# STM32F7.net
KiCad netlist of a schematic drawn in Altium Designer
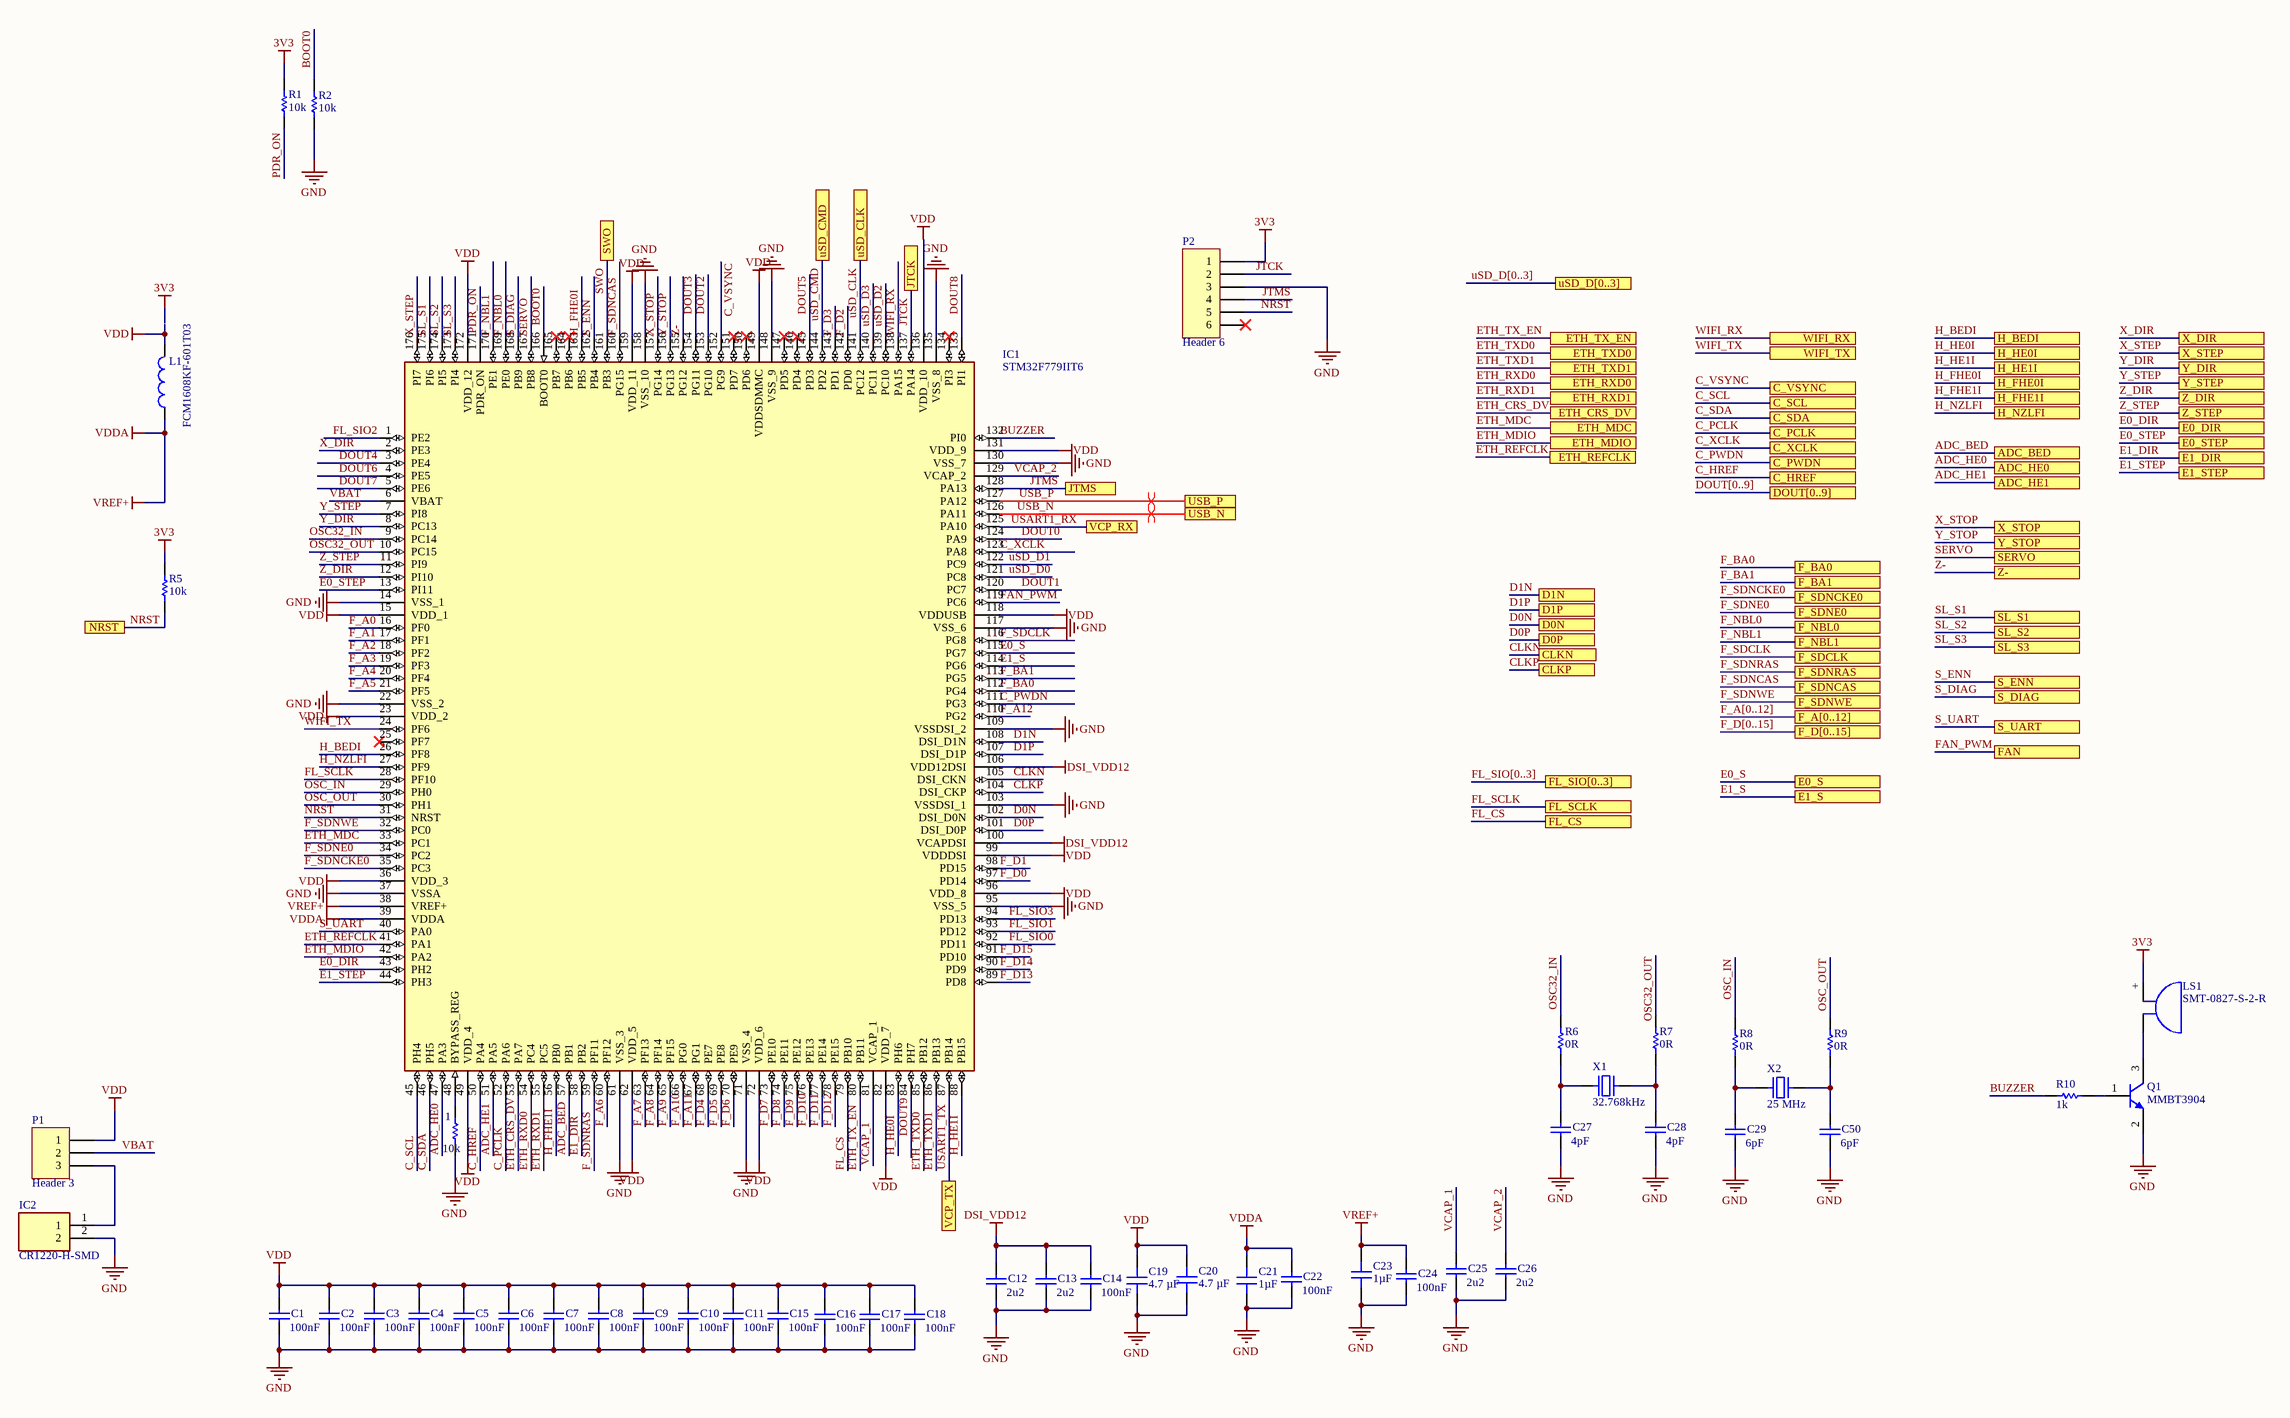
[diagram p0: STM32F7.SchDoc]

(export (version "E")
  (design (tool "Eeschema 10.0.6"))
  (components
    (comp (ref "1")
      (value "10k")
      (footprint "1608[0603]")
      (description "Resistor")
      (fields (field (name "Comment") "Res1") (field (name "PUBLISHER") "Altium Limited"))
      (libsource (lib "Miscellaneous Devices") (part "Res1"))
    )
    (comp (ref "C1")
      (value "100nF")
      (footprint "1608[0603]")
      (description "Capacitor")
      (fields (field (name "Comment") "X5R") (field (name "PUBLISHER") "Altium Limited"))
      (libsource (lib "Miscellaneous Devices") (part "Cap"))
    )
    (comp (ref "C2")
      (value "100nF")
      (footprint "1608[0603]")
      (description "Capacitor")
      (fields (field (name "Comment") "X5R") (field (name "PUBLISHER") "Altium Limited"))
      (libsource (lib "Miscellaneous Devices") (part "Cap"))
    )
    (comp (ref "C3")
      (value "100nF")
      (footprint "1608[0603]")
      (description "Capacitor")
      (fields (field (name "Comment") "X5R") (field (name "PUBLISHER") "Altium Limited"))
      (libsource (lib "Miscellaneous Devices") (part "Cap"))
    )
    (comp (ref "C4")
      (value "100nF")
      (footprint "1608[0603]")
      (description "Capacitor")
      (fields (field (name "Comment") "X5R") (field (name "PUBLISHER") "Altium Limited"))
      (libsource (lib "Miscellaneous Devices") (part "Cap"))
    )
    (comp (ref "C5")
      (value "100nF")
      (footprint "1608[0603]")
      (description "Capacitor")
      (fields (field (name "Comment") "X5R") (field (name "PUBLISHER") "Altium Limited"))
      (libsource (lib "Miscellaneous Devices") (part "Cap"))
    )
    (comp (ref "C6")
      (value "100nF")
      (footprint "1608[0603]")
      (description "Capacitor")
      (fields (field (name "Comment") "X5R") (field (name "PUBLISHER") "Altium Limited"))
      (libsource (lib "Miscellaneous Devices") (part "Cap"))
    )
    (comp (ref "C7")
      (value "100nF")
      (footprint "1608[0603]")
      (description "Capacitor")
      (fields (field (name "Comment") "X5R") (field (name "PUBLISHER") "Altium Limited"))
      (libsource (lib "Miscellaneous Devices") (part "Cap"))
    )
    (comp (ref "C8")
      (value "100nF")
      (footprint "1608[0603]")
      (description "Capacitor")
      (fields (field (name "Comment") "X5R") (field (name "PUBLISHER") "Altium Limited"))
      (libsource (lib "Miscellaneous Devices") (part "Cap"))
    )
    (comp (ref "C9")
      (value "100nF")
      (footprint "1608[0603]")
      (description "Capacitor")
      (fields (field (name "Comment") "X5R") (field (name "PUBLISHER") "Altium Limited"))
      (libsource (lib "Miscellaneous Devices") (part "Cap"))
    )
    (comp (ref "C10")
      (value "100nF")
      (footprint "1608[0603]")
      (description "Capacitor")
      (fields (field (name "Comment") "X5R") (field (name "PUBLISHER") "Altium Limited"))
      (libsource (lib "Miscellaneous Devices") (part "Cap"))
    )
    (comp (ref "C11")
      (value "100nF")
      (footprint "1608[0603]")
      (description "Capacitor")
      (fields (field (name "Comment") "X5R") (field (name "PUBLISHER") "Altium Limited"))
      (libsource (lib "Miscellaneous Devices") (part "Cap"))
    )
    (comp (ref "C12")
      (value "2u2")
      (footprint "1608[0603]")
      (description "Capacitor")
      (fields (field (name "Comment") "X5R") (field (name "PUBLISHER") "Altium Limited"))
      (libsource (lib "Miscellaneous Devices") (part "Cap"))
    )
    (comp (ref "C13")
      (value "2u2")
      (footprint "1608[0603]")
      (description "Capacitor")
      (fields (field (name "Comment") "X5R") (field (name "PUBLISHER") "Altium Limited"))
      (libsource (lib "Miscellaneous Devices") (part "Cap"))
    )
    (comp (ref "C14")
      (value "100nF")
      (footprint "1608[0603]")
      (description "Capacitor")
      (fields (field (name "Comment") "X5R") (field (name "PUBLISHER") "Altium Limited"))
      (libsource (lib "Miscellaneous Devices") (part "Cap"))
    )
    (comp (ref "C15")
      (value "100nF")
      (footprint "1608[0603]")
      (description "Capacitor")
      (fields (field (name "Comment") "X5R") (field (name "PUBLISHER") "Altium Limited"))
      (libsource (lib "Miscellaneous Devices") (part "Cap"))
    )
    (comp (ref "C16")
      (value "100nF")
      (footprint "1608[0603]")
      (description "Capacitor")
      (fields (field (name "Comment") "X5R") (field (name "PUBLISHER") "Altium Limited"))
      (libsource (lib "Miscellaneous Devices") (part "Cap"))
    )
    (comp (ref "C17")
      (value "100nF")
      (footprint "1608[0603]")
      (description "Capacitor")
      (fields (field (name "Comment") "X5R") (field (name "PUBLISHER") "Altium Limited"))
      (libsource (lib "Miscellaneous Devices") (part "Cap"))
    )
    (comp (ref "C18")
      (value "100nF")
      (footprint "1608[0603]")
      (description "Capacitor")
      (fields (field (name "Comment") "X5R") (field (name "PUBLISHER") "Altium Limited"))
      (libsource (lib "Miscellaneous Devices") (part "Cap"))
    )
    (comp (ref "C19")
      (value "4.7 µF")
      (footprint "CAP 0603_1608")
      (description "CAP CER 4.7UF 16V X5R 0603")
      (fields
        (field (name "PART NUMBER") "GRM185R61C475KE11D")
        (field (name "MANUFACTURER") "Murata Electronics")
      )
      (libsource (lib "Celestial Altium Library - altium_library") (part "Capacitor"))
    )
    (comp (ref "C20")
      (value "4.7 µF")
      (footprint "CAP 0603_1608")
      (description "CAP CER 4.7UF 16V X5R 0603")
      (fields
        (field (name "PART NUMBER") "GRM185R61C475KE11D")
        (field (name "MANUFACTURER") "Murata Electronics")
      )
      (libsource (lib "Celestial Altium Library - altium_library") (part "Capacitor"))
    )
    (comp (ref "C21")
      (value "1µF")
      (footprint "CAP 0603_1608")
      (description "CAP CER 1UF 16V X5R 0603")
      (fields (field (name "PART NUMBER") "0603YD105KAT4A") (field (name "MANUFACTURER") "AVX Corporation"))
      (libsource (lib "Celestial Altium Library - altium_library") (part "Capacitor"))
    )
    (comp (ref "C22")
      (value "100nF")
      (footprint "1608[0603]")
      (description "Capacitor")
      (fields (field (name "Comment") "X5R") (field (name "PUBLISHER") "Altium Limited"))
      (libsource (lib "Miscellaneous Devices") (part "Cap"))
    )
    (comp (ref "C23")
      (value "1µF")
      (footprint "CAP 0603_1608")
      (description "CAP CER 1UF 16V X5R 0603")
      (fields (field (name "PART NUMBER") "0603YD105KAT4A") (field (name "MANUFACTURER") "AVX Corporation"))
      (libsource (lib "Celestial Altium Library - altium_library") (part "Capacitor"))
    )
    (comp (ref "C24")
      (value "100nF")
      (footprint "1608[0603]")
      (description "Capacitor")
      (fields (field (name "Comment") "X5R") (field (name "PUBLISHER") "Altium Limited"))
      (libsource (lib "Miscellaneous Devices") (part "Cap"))
    )
    (comp (ref "C25")
      (value "2u2")
      (footprint "1608[0603]")
      (description "Capacitor")
      (fields (field (name "Comment") "X5R") (field (name "PUBLISHER") "Altium Limited"))
      (libsource (lib "Miscellaneous Devices") (part "Cap"))
    )
    (comp (ref "C26")
      (value "2u2")
      (footprint "1608[0603]")
      (description "Capacitor")
      (fields (field (name "Comment") "X5R") (field (name "PUBLISHER") "Altium Limited"))
      (libsource (lib "Miscellaneous Devices") (part "Cap"))
    )
    (comp (ref "C27")
      (value "4pF")
      (footprint "1608[0603]")
      (description "Capacitor")
      (fields (field (name "Comment") "X5R") (field (name "PUBLISHER") "Altium Limited"))
      (libsource (lib "Miscellaneous Devices") (part "Cap"))
    )
    (comp (ref "C28")
      (value "4pF")
      (footprint "1608[0603]")
      (description "Capacitor")
      (fields (field (name "Comment") "X5R") (field (name "PUBLISHER") "Altium Limited"))
      (libsource (lib "Miscellaneous Devices") (part "Cap"))
    )
    (comp (ref "C29")
      (value "6pF")
      (footprint "1608[0603]")
      (description "Capacitor")
      (fields (field (name "Comment") "X5R") (field (name "PUBLISHER") "Altium Limited"))
      (libsource (lib "Miscellaneous Devices") (part "Cap"))
    )
    (comp (ref "C50")
      (value "6pF")
      (footprint "1608[0603]")
      (description "Capacitor")
      (fields (field (name "Comment") "X5R") (field (name "PUBLISHER") "Altium Limited"))
      (libsource (lib "Miscellaneous Devices") (part "Cap"))
    )
    (comp (ref "IC1")
      (value "STM32F779IIT6")
      (footprint "SamacSys:QFP50P2600X2600X160-176N")
      (description "Integrated Circuit")
      (fields (field (name "MOUSER PART NUMBER") "511-STM32F779IIT6"))
      (libsource (lib "*") (part "STM32F779IIT6"))
    )
    (comp (ref "IC2")
      (value "CR1220-H-SMD")
      (footprint "SamacSys:CR1220HSMD")
      (description "Integrated Circuit")
      (libsource (lib "*") (part "CR1220-H-SMD"))
    )
    (comp (ref "L1")
      (value "FCM1608KF-601T03")
      (footprint "0603L")
      (description "Inductor")
      (fields (field (name "PUBLISHER") "Altium Limited"))
      (libsource (lib "MB1137") (part "Inductor"))
    )
    (comp (ref "LS1")
      (value "SMT-0827-S-2-R")
      (footprint "PUI Audio SMT-0827-S-2-R")
      (description "AUDIO MAGNETIC XDCR 2.5-4.5V SMD")
      (fields (field (name "MANUFACTURER") "PUI Audio, Inc."))
      (libsource (lib "Celestial Altium Library - altium_library") (part "Buzzer 2 pin"))
    )
    (comp (ref "P1")
      (value "Header 3")
      (footprint "HDR1X3")
      (description "Header, 3-Pin")
      (fields (field (name "PUBLISHER") "Altium Limited"))
      (libsource (lib "Miscellaneous Connectors") (part "Header 3"))
    )
    (comp (ref "P2")
      (value "Header 6")
      (footprint "HDR1X6")
      (description "Header, 6-Pin")
      (fields (field (name "PUBLISHER") "Altium Limited"))
      (libsource (lib "Miscellaneous Connectors") (part "Header 6"))
    )
    (comp (ref "Q1")
      (value "MMBT3904")
      (footprint "SOT-23_N")
      (description "TRANS NPN 40V 0.2A SOT416")
      (fields (field (name "PART NUMBER") "MMBT3904TT1G") (field (name "MANUFACTURER") "ON Semiconductor"))
      (libsource (lib "Celestial Altium Library - altium_library") (part "ON SEMI NPN SC-75"))
    )
    (comp (ref "R1")
      (value "10k")
      (footprint "1608[0603]")
      (description "Resistor")
      (fields (field (name "Comment") "Res1") (field (name "PUBLISHER") "Altium Limited"))
      (libsource (lib "Miscellaneous Devices") (part "Res1"))
    )
    (comp (ref "R2")
      (value "10k")
      (footprint "1608[0603]")
      (description "Resistor")
      (fields (field (name "Comment") "Res1") (field (name "PUBLISHER") "Altium Limited"))
      (libsource (lib "Miscellaneous Devices") (part "Res1"))
    )
    (comp (ref "R5")
      (value "10k")
      (footprint "1608[0603]")
      (description "Resistor")
      (fields (field (name "Comment") "Res1") (field (name "PUBLISHER") "Altium Limited"))
      (libsource (lib "Miscellaneous Devices") (part "Res1"))
    )
    (comp (ref "R6")
      (value "0R")
      (footprint "1608[0603]")
      (description "Resistor")
      (fields (field (name "Comment") "Res1") (field (name "PUBLISHER") "Altium Limited"))
      (libsource (lib "Miscellaneous Devices") (part "Res1"))
    )
    (comp (ref "R7")
      (value "0R")
      (footprint "1608[0603]")
      (description "Resistor")
      (fields (field (name "Comment") "Res1") (field (name "PUBLISHER") "Altium Limited"))
      (libsource (lib "Miscellaneous Devices") (part "Res1"))
    )
    (comp (ref "R8")
      (value "0R")
      (footprint "1608[0603]")
      (description "Resistor")
      (fields (field (name "Comment") "Res1") (field (name "PUBLISHER") "Altium Limited"))
      (libsource (lib "Miscellaneous Devices") (part "Res1"))
    )
    (comp (ref "R9")
      (value "0R")
      (footprint "1608[0603]")
      (description "Resistor")
      (fields (field (name "Comment") "Res1") (field (name "PUBLISHER") "Altium Limited"))
      (libsource (lib "Miscellaneous Devices") (part "Res1"))
    )
    (comp (ref "R10")
      (value "1k")
      (footprint "1608[0603]")
      (description "Resistor")
      (fields (field (name "Comment") "Res1") (field (name "PUBLISHER") "Altium Limited"))
      (libsource (lib "Miscellaneous Devices") (part "Res1"))
    )
    (comp (ref "X1")
      (value "32.768kHz")
      (footprint "NDK NX5032GA")
      (description "CRYSTAL 25.0000MHZ 8PF SMD")
      (fields
        (field (name "PART NUMBER") "NX5032GA-25.000000MHZ-LN-CD-1")
        (field (name "MANUFACTURER") "NDK America, Inc.")
      )
      (libsource (lib "Celestial Altium Library - altium_library") (part "NDK Crystal NX5032GA"))
    )
    (comp (ref "X2")
      (value "25 MHz")
      (footprint "NDK NX5032GA")
      (description "CRYSTAL 25.0000MHZ 8PF SMD")
      (fields
        (field (name "PART NUMBER") "NX5032GA-25.000000MHZ-LN-CD-1")
        (field (name "MANUFACTURER") "NDK America, Inc.")
      )
      (libsource (lib "Celestial Altium Library - altium_library") (part "NDK Crystal NX5032GA"))
    )
  )
  (nets
    (net (code "1") (name "/ADC_BED") (class "Default")
      (node (ref "IC1") (pin "57") (pinfunction "PB1_57") (pintype "bidirectional"))
    )
    (net (code "2") (name "/ADC_HE0") (class "Default")
      (node (ref "IC1") (pin "47") (pinfunction "PA3_47") (pintype "bidirectional"))
    )
    (net (code "3") (name "/ADC_HE1") (class "Default")
      (node (ref "IC1") (pin "51") (pinfunction "PA5_51") (pintype "bidirectional"))
    )
    (net (code "4") (name "/BOOT0") (class "Default")
      (node (ref "IC1") (pin "166") (pinfunction "BOOT0_166") (pintype "input"))
      (node (ref "R2") (pin "1") (pinfunction "1_1") (pintype "passive"))
    )
    (net (code "5") (name "/BUZZER") (class "Default")
      (node (ref "IC1") (pin "132") (pinfunction "PI0_132") (pintype "bidirectional"))
      (node (ref "R10") (pin "1") (pinfunction "1_1") (pintype "passive"))
    )
    (net (code "6") (name "/CLKN") (class "Default")
      (node (ref "IC1") (pin "105") (pinfunction "DSI_CKN_105") (pintype "bidirectional"))
    )
    (net (code "7") (name "/CLKP") (class "Default")
      (node (ref "IC1") (pin "104") (pinfunction "DSI_CKP_104") (pintype "bidirectional"))
    )
    (net (code "8") (name "/C_HREF") (class "Default")
      (node (ref "IC1") (pin "50") (pinfunction "PA4_50") (pintype "bidirectional"))
    )
    (net (code "9") (name "/C_PCLK") (class "Default")
      (node (ref "IC1") (pin "52") (pinfunction "PA6_52") (pintype "bidirectional"))
    )
    (net (code "10") (name "/C_PWDN") (class "Default")
      (node (ref "IC1") (pin "111") (pinfunction "PG3_111") (pintype "bidirectional"))
    )
    (net (code "11") (name "/C_SCL") (class "Default")
      (node (ref "IC1") (pin "45") (pinfunction "PH4_45") (pintype "bidirectional"))
    )
    (net (code "12") (name "/C_SDA") (class "Default")
      (node (ref "IC1") (pin "46") (pinfunction "PH5_46") (pintype "bidirectional"))
    )
    (net (code "13") (name "/C_VSYNC") (class "Default")
      (node (ref "IC1") (pin "152") (pinfunction "PG9_152") (pintype "bidirectional"))
    )
    (net (code "14") (name "/C_XCLK") (class "Default")
      (node (ref "IC1") (pin "123") (pinfunction "PA8_123") (pintype "bidirectional"))
    )
    (net (code "15") (name "/D0N") (class "Default")
      (node (ref "IC1") (pin "102") (pinfunction "DSI_D0N_102") (pintype "bidirectional"))
    )
    (net (code "16") (name "/D0P") (class "Default")
      (node (ref "IC1") (pin "101") (pinfunction "DSI_D0P_101") (pintype "bidirectional"))
    )
    (net (code "17") (name "/D1N") (class "Default")
      (node (ref "IC1") (pin "108") (pinfunction "DSI_D1N_108") (pintype "bidirectional"))
    )
    (net (code "18") (name "/D1P") (class "Default")
      (node (ref "IC1") (pin "107") (pinfunction "DSI_D1P_107") (pintype "bidirectional"))
    )
    (net (code "19") (name "/DOUT0") (class "Default")
      (node (ref "IC1") (pin "124") (pinfunction "PA9_124") (pintype "bidirectional"))
    )
    (net (code "20") (name "/DOUT1") (class "Default")
      (node (ref "IC1") (pin "120") (pinfunction "PC7_120") (pintype "bidirectional"))
    )
    (net (code "21") (name "/DOUT2") (class "Default")
      (node (ref "IC1") (pin "153") (pinfunction "PG10_153") (pintype "bidirectional"))
    )
    (net (code "22") (name "/DOUT3") (class "Default")
      (node (ref "IC1") (pin "154") (pinfunction "PG11_154") (pintype "bidirectional"))
    )
    (net (code "23") (name "/DOUT4") (class "Default")
      (node (ref "IC1") (pin "3") (pinfunction "PE4_3") (pintype "bidirectional"))
    )
    (net (code "24") (name "/DOUT5") (class "Default")
      (node (ref "IC1") (pin "145") (pinfunction "PD3_145") (pintype "bidirectional"))
    )
    (net (code "25") (name "/DOUT6") (class "Default")
      (node (ref "IC1") (pin "4") (pinfunction "PE5_4") (pintype "bidirectional"))
    )
    (net (code "26") (name "/DOUT7") (class "Default")
      (node (ref "IC1") (pin "5") (pinfunction "PE6_5") (pintype "bidirectional"))
    )
    (net (code "27") (name "/DOUT8") (class "Default")
      (node (ref "IC1") (pin "133") (pinfunction "PI1_133") (pintype "bidirectional"))
    )
    (net (code "28") (name "/DOUT9") (class "Default")
      (node (ref "IC1") (pin "84") (pinfunction "PH7_84") (pintype "bidirectional"))
    )
    (net (code "30") (name "/E0_DIR") (class "Default")
      (node (ref "IC1") (pin "43") (pinfunction "PH2_43") (pintype "bidirectional"))
    )
    (net (code "31") (name "/E0_S") (class "Default")
      (node (ref "IC1") (pin "115") (pinfunction "PG7_115") (pintype "bidirectional"))
    )
    (net (code "32") (name "/E0_STEP") (class "Default")
      (node (ref "IC1") (pin "13") (pinfunction "PI11_13") (pintype "bidirectional"))
    )
    (net (code "33") (name "/E1_DIR") (class "Default")
      (node (ref "IC1") (pin "58") (pinfunction "PB2_58") (pintype "bidirectional"))
    )
    (net (code "34") (name "/E1_S") (class "Default")
      (node (ref "IC1") (pin "114") (pinfunction "PG6_114") (pintype "bidirectional"))
    )
    (net (code "35") (name "/E1_STEP") (class "Default")
      (node (ref "IC1") (pin "44") (pinfunction "PH3_44") (pintype "bidirectional"))
    )
    (net (code "36") (name "/ETH_CRS_DV") (class "Default")
      (node (ref "IC1") (pin "53") (pinfunction "PA7_53") (pintype "bidirectional"))
    )
    (net (code "37") (name "/ETH_MDC") (class "Default")
      (node (ref "IC1") (pin "33") (pinfunction "PC1_33") (pintype "bidirectional"))
    )
    (net (code "38") (name "/ETH_MDIO") (class "Default")
      (node (ref "IC1") (pin "42") (pinfunction "PA2_42") (pintype "bidirectional"))
    )
    (net (code "39") (name "/ETH_REFCLK") (class "Default")
      (node (ref "IC1") (pin "41") (pinfunction "PA1_41") (pintype "bidirectional"))
    )
    (net (code "40") (name "/ETH_RXD0") (class "Default")
      (node (ref "IC1") (pin "54") (pinfunction "PC4_54") (pintype "bidirectional"))
    )
    (net (code "41") (name "/ETH_RXD1") (class "Default")
      (node (ref "IC1") (pin "55") (pinfunction "PC5_55") (pintype "bidirectional"))
    )
    (net (code "42") (name "/ETH_TXD0") (class "Default")
      (node (ref "IC1") (pin "85") (pinfunction "PB12_85") (pintype "bidirectional"))
    )
    (net (code "43") (name "/ETH_TXD1") (class "Default")
      (node (ref "IC1") (pin "86") (pinfunction "PB13_86") (pintype "bidirectional"))
    )
    (net (code "44") (name "/ETH_TX_EN") (class "Default")
      (node (ref "IC1") (pin "80") (pinfunction "PB11_80") (pintype "bidirectional"))
    )
    (net (code "45") (name "/FAN_PWM") (class "Default")
      (node (ref "IC1") (pin "119") (pinfunction "PC6_119") (pintype "bidirectional"))
    )
    (net (code "46") (name "/FL_CS") (class "Default")
      (node (ref "IC1") (pin "79") (pinfunction "PB10_79") (pintype "bidirectional"))
    )
    (net (code "47") (name "/FL_SCLK") (class "Default")
      (node (ref "IC1") (pin "28") (pinfunction "PF10_28") (pintype "bidirectional"))
    )
    (net (code "48") (name "/FL_SIO0") (class "Default")
      (node (ref "IC1") (pin "92") (pinfunction "PD11_92") (pintype "bidirectional"))
    )
    (net (code "49") (name "/FL_SIO1") (class "Default")
      (node (ref "IC1") (pin "93") (pinfunction "PD12_93") (pintype "bidirectional"))
    )
    (net (code "50") (name "/FL_SIO2") (class "Default")
      (node (ref "IC1") (pin "1") (pinfunction "PE2_1") (pintype "bidirectional"))
    )
    (net (code "51") (name "/FL_SIO3") (class "Default")
      (node (ref "IC1") (pin "94") (pinfunction "PD13_94") (pintype "bidirectional"))
    )
    (net (code "53") (name "/F_A0") (class "Default")
      (node (ref "IC1") (pin "16") (pinfunction "PF0_16") (pintype "bidirectional"))
    )
    (net (code "54") (name "/F_A1") (class "Default")
      (node (ref "IC1") (pin "17") (pinfunction "PF1_17") (pintype "bidirectional"))
    )
    (net (code "55") (name "/F_A2") (class "Default")
      (node (ref "IC1") (pin "18") (pinfunction "PF2_18") (pintype "bidirectional"))
    )
    (net (code "56") (name "/F_A3") (class "Default")
      (node (ref "IC1") (pin "19") (pinfunction "PF3_19") (pintype "bidirectional"))
    )
    (net (code "57") (name "/F_A4") (class "Default")
      (node (ref "IC1") (pin "20") (pinfunction "PF4_20") (pintype "bidirectional"))
    )
    (net (code "58") (name "/F_A5") (class "Default")
      (node (ref "IC1") (pin "21") (pinfunction "PF5_21") (pintype "bidirectional"))
    )
    (net (code "59") (name "/F_A6") (class "Default")
      (node (ref "IC1") (pin "60") (pinfunction "PF12_60") (pintype "bidirectional"))
    )
    (net (code "60") (name "/F_A7") (class "Default")
      (node (ref "IC1") (pin "63") (pinfunction "PF13_63") (pintype "bidirectional"))
    )
    (net (code "61") (name "/F_A8") (class "Default")
      (node (ref "IC1") (pin "64") (pinfunction "PF14_64") (pintype "bidirectional"))
    )
    (net (code "62") (name "/F_A9") (class "Default")
      (node (ref "IC1") (pin "65") (pinfunction "PF15_65") (pintype "bidirectional"))
    )
    (net (code "63") (name "/F_A10") (class "Default")
      (node (ref "IC1") (pin "66") (pinfunction "PG0_66") (pintype "bidirectional"))
    )
    (net (code "64") (name "/F_A11") (class "Default")
      (node (ref "IC1") (pin "67") (pinfunction "PG1_67") (pintype "bidirectional"))
    )
    (net (code "65") (name "/F_A12") (class "Default")
      (node (ref "IC1") (pin "110") (pinfunction "PG2_110") (pintype "bidirectional"))
    )
    (net (code "67") (name "/F_BA0") (class "Default")
      (node (ref "IC1") (pin "112") (pinfunction "PG4_112") (pintype "bidirectional"))
    )
    (net (code "68") (name "/F_BA1") (class "Default")
      (node (ref "IC1") (pin "113") (pinfunction "PG5_113") (pintype "bidirectional"))
    )
    (net (code "69") (name "/F_D0") (class "Default")
      (node (ref "IC1") (pin "97") (pinfunction "PD14_97") (pintype "bidirectional"))
    )
    (net (code "70") (name "/F_D1") (class "Default")
      (node (ref "IC1") (pin "98") (pinfunction "PD15_98") (pintype "bidirectional"))
    )
    (net (code "71") (name "/F_D2") (class "Default")
      (node (ref "IC1") (pin "142") (pinfunction "PD0_142") (pintype "bidirectional"))
    )
    (net (code "72") (name "/F_D3") (class "Default")
      (node (ref "IC1") (pin "143") (pinfunction "PD1_143") (pintype "bidirectional"))
    )
    (net (code "73") (name "/F_D4") (class "Default")
      (node (ref "IC1") (pin "68") (pinfunction "PE7_68") (pintype "bidirectional"))
    )
    (net (code "74") (name "/F_D5") (class "Default")
      (node (ref "IC1") (pin "69") (pinfunction "PE8_69") (pintype "bidirectional"))
    )
    (net (code "75") (name "/F_D6") (class "Default")
      (node (ref "IC1") (pin "70") (pinfunction "PE9_70") (pintype "bidirectional"))
    )
    (net (code "76") (name "/F_D7") (class "Default")
      (node (ref "IC1") (pin "73") (pinfunction "PE10_73") (pintype "bidirectional"))
    )
    (net (code "77") (name "/F_D8") (class "Default")
      (node (ref "IC1") (pin "74") (pinfunction "PE11_74") (pintype "bidirectional"))
    )
    (net (code "78") (name "/F_D9") (class "Default")
      (node (ref "IC1") (pin "75") (pinfunction "PE12_75") (pintype "bidirectional"))
    )
    (net (code "79") (name "/F_D10") (class "Default")
      (node (ref "IC1") (pin "76") (pinfunction "PE13_76") (pintype "bidirectional"))
    )
    (net (code "80") (name "/F_D11") (class "Default")
      (node (ref "IC1") (pin "77") (pinfunction "PE14_77") (pintype "bidirectional"))
    )
    (net (code "81") (name "/F_D12") (class "Default")
      (node (ref "IC1") (pin "78") (pinfunction "PE15_78") (pintype "bidirectional"))
    )
    (net (code "82") (name "/F_D13") (class "Default")
      (node (ref "IC1") (pin "89") (pinfunction "PD8_89") (pintype "bidirectional"))
    )
    (net (code "83") (name "/F_D14") (class "Default")
      (node (ref "IC1") (pin "90") (pinfunction "PD9_90") (pintype "bidirectional"))
    )
    (net (code "84") (name "/F_D15") (class "Default")
      (node (ref "IC1") (pin "91") (pinfunction "PD10_91") (pintype "bidirectional"))
    )
    (net (code "86") (name "/F_NBL0") (class "Default")
      (node (ref "IC1") (pin "169") (pinfunction "PE0_169") (pintype "bidirectional"))
    )
    (net (code "87") (name "/F_NBL1") (class "Default")
      (node (ref "IC1") (pin "170") (pinfunction "PE1_170") (pintype "bidirectional"))
    )
    (net (code "88") (name "/F_SDCLK") (class "Default")
      (node (ref "IC1") (pin "116") (pinfunction "PG8_116") (pintype "bidirectional"))
    )
    (net (code "89") (name "/F_SDNCAS") (class "Default")
      (node (ref "IC1") (pin "160") (pinfunction "PG15_160") (pintype "bidirectional"))
    )
    (net (code "90") (name "/F_SDNCKE0") (class "Default")
      (node (ref "IC1") (pin "35") (pinfunction "PC3_35") (pintype "bidirectional"))
    )
    (net (code "91") (name "/F_SDNE0") (class "Default")
      (node (ref "IC1") (pin "34") (pinfunction "PC2_34") (pintype "bidirectional"))
    )
    (net (code "92") (name "/F_SDNRAS") (class "Default")
      (node (ref "IC1") (pin "59") (pinfunction "PF11_59") (pintype "bidirectional"))
    )
    (net (code "93") (name "/F_SDNWE") (class "Default")
      (node (ref "IC1") (pin "32") (pinfunction "PC0_32") (pintype "bidirectional"))
    )
    (net (code "94") (name "/H_BEDI") (class "Default")
      (node (ref "IC1") (pin "26") (pinfunction "PF8_26") (pintype "bidirectional"))
    )
    (net (code "95") (name "/H_FHE0I") (class "Default")
      (node (ref "IC1") (pin "163") (pinfunction "PB5_163") (pintype "bidirectional"))
    )
    (net (code "96") (name "/H_FHE1I") (class "Default")
      (node (ref "IC1") (pin "56") (pinfunction "PB0_56") (pintype "bidirectional"))
    )
    (net (code "97") (name "/H_HE0I") (class "Default")
      (node (ref "IC1") (pin "83") (pinfunction "PH6_83") (pintype "bidirectional"))
    )
    (net (code "98") (name "/H_HE1I") (class "Default")
      (node (ref "IC1") (pin "88") (pinfunction "PB15_88") (pintype "bidirectional"))
    )
    (net (code "99") (name "/H_NZLFI") (class "Default")
      (node (ref "IC1") (pin "27") (pinfunction "PF9_27") (pintype "bidirectional"))
    )
    (net (code "100") (name "/JTCK") (class "Default")
      (node (ref "IC1") (pin "137") (pinfunction "PA14_137") (pintype "bidirectional"))
      (node (ref "P2") (pin "2") (pinfunction "2_2") (pintype "passive"))
    )
    (net (code "101") (name "/JTMS") (class "Default")
      (node (ref "IC1") (pin "128") (pinfunction "PA13_128") (pintype "bidirectional"))
      (node (ref "P2") (pin "4") (pinfunction "4_4") (pintype "passive"))
    )
    (net (code "102") (name "/NRST") (class "Default")
      (node (ref "IC1") (pin "31") (pinfunction "NRST_31") (pintype "bidirectional"))
      (node (ref "P2") (pin "5") (pinfunction "5_5") (pintype "passive"))
      (node (ref "R5") (pin "2") (pinfunction "2_2") (pintype "passive"))
    )
    (net (code "103") (name "/OSC32_IN") (class "Default")
      (node (ref "IC1") (pin "9") (pinfunction "PC14_9") (pintype "bidirectional"))
      (node (ref "R6") (pin "1") (pinfunction "1_1") (pintype "passive"))
    )
    (net (code "104") (name "/OSC32_OUT") (class "Default")
      (node (ref "IC1") (pin "10") (pinfunction "PC15_10") (pintype "bidirectional"))
      (node (ref "R7") (pin "1") (pinfunction "1_1") (pintype "passive"))
    )
    (net (code "105") (name "/OSC_IN") (class "Default")
      (node (ref "IC1") (pin "29") (pinfunction "PH0_29") (pintype "bidirectional"))
      (node (ref "R8") (pin "1") (pinfunction "1_1") (pintype "passive"))
    )
    (net (code "106") (name "/OSC_OUT") (class "Default")
      (node (ref "IC1") (pin "30") (pinfunction "PH1_30") (pintype "bidirectional"))
      (node (ref "R9") (pin "1") (pinfunction "1_1") (pintype "passive"))
    )
    (net (code "107") (name "/PDR_ON") (class "Default")
      (node (ref "IC1") (pin "171") (pinfunction "PDR_ON_171") (pintype "power_in"))
      (node (ref "R1") (pin "2") (pinfunction "2_2") (pintype "passive"))
    )
    (net (code "108") (name "/SERVO") (class "Default")
      (node (ref "IC1") (pin "167") (pinfunction "PB8_167") (pintype "bidirectional"))
    )
    (net (code "109") (name "/SL_S1") (class "Default")
      (node (ref "IC1") (pin "175") (pinfunction "PI6_175") (pintype "bidirectional"))
    )
    (net (code "110") (name "/SL_S2") (class "Default")
      (node (ref "IC1") (pin "174") (pinfunction "PI5_174") (pintype "bidirectional"))
    )
    (net (code "111") (name "/SL_S3") (class "Default")
      (node (ref "IC1") (pin "173") (pinfunction "PI4_173") (pintype "bidirectional"))
    )
    (net (code "112") (name "/SWO") (class "Default")
      (node (ref "IC1") (pin "161") (pinfunction "PB3_161") (pintype "bidirectional"))
    )
    (net (code "113") (name "/S_DIAG") (class "Default")
      (node (ref "IC1") (pin "168") (pinfunction "PB9_168") (pintype "bidirectional"))
    )
    (net (code "114") (name "/S_ENN") (class "Default")
      (node (ref "IC1") (pin "162") (pinfunction "PB4_162") (pintype "bidirectional"))
    )
    (net (code "115") (name "/S_UART") (class "Default")
      (node (ref "IC1") (pin "40") (pinfunction "PA0_40") (pintype "bidirectional"))
    )
    (net (code "116") (name "/USART1_RX") (class "Default")
      (node (ref "IC1") (pin "125") (pinfunction "PA10_125") (pintype "bidirectional"))
    )
    (net (code "117") (name "/USART1_TX") (class "Default")
      (node (ref "IC1") (pin "87") (pinfunction "PB14_87") (pintype "bidirectional"))
    )
    (net (code "118") (name "/USB_N") (class "Default")
      (node (ref "IC1") (pin "126") (pinfunction "PA11_126") (pintype "bidirectional"))
    )
    (net (code "119") (name "/USB_P") (class "Default")
      (node (ref "IC1") (pin "127") (pinfunction "PA12_127") (pintype "bidirectional"))
    )
    (net (code "120") (name "/VBAT") (class "Default")
      (node (ref "IC1") (pin "6") (pinfunction "VBAT_6") (pintype "power_in"))
      (node (ref "P1") (pin "2") (pinfunction "2_2") (pintype "passive"))
    )
    (net (code "121") (name "/VCAP_1") (class "Default")
      (node (ref "C25") (pin "1") (pinfunction "1_1") (pintype "passive"))
      (node (ref "IC1") (pin "81") (pinfunction "VCAP_1_81") (pintype "power_in"))
    )
    (net (code "122") (name "/VCAP_2") (class "Default")
      (node (ref "C26") (pin "1") (pinfunction "1_1") (pintype "passive"))
      (node (ref "IC1") (pin "129") (pinfunction "VCAP_2_129") (pintype "power_in"))
    )
    (net (code "123") (name "/WIFI_RX") (class "Default")
      (node (ref "IC1") (pin "138") (pinfunction "PA15_138") (pintype "bidirectional"))
    )
    (net (code "124") (name "/WIFI_TX") (class "Default")
      (node (ref "IC1") (pin "24") (pinfunction "PF6_24") (pintype "bidirectional"))
    )
    (net (code "125") (name "/X_DIR") (class "Default")
      (node (ref "IC1") (pin "2") (pinfunction "PE3_2") (pintype "bidirectional"))
    )
    (net (code "126") (name "/X_STEP") (class "Default")
      (node (ref "IC1") (pin "176") (pinfunction "PI7_176") (pintype "bidirectional"))
    )
    (net (code "127") (name "/X_STOP") (class "Default")
      (node (ref "IC1") (pin "157") (pinfunction "PG14_157") (pintype "bidirectional"))
    )
    (net (code "128") (name "/Y_DIR") (class "Default")
      (node (ref "IC1") (pin "8") (pinfunction "PC13_8") (pintype "bidirectional"))
    )
    (net (code "129") (name "/Y_STEP") (class "Default")
      (node (ref "IC1") (pin "7") (pinfunction "PI8_7") (pintype "bidirectional"))
    )
    (net (code "130") (name "/Y_STOP") (class "Default")
      (node (ref "IC1") (pin "156") (pinfunction "PG13_156") (pintype "bidirectional"))
    )
    (net (code "131") (name "/Z-") (class "Default")
      (node (ref "IC1") (pin "155") (pinfunction "PG12_155") (pintype "bidirectional"))
    )
    (net (code "132") (name "/Z_DIR") (class "Default")
      (node (ref "IC1") (pin "12") (pinfunction "PI10_12") (pintype "bidirectional"))
    )
    (net (code "133") (name "/Z_STEP") (class "Default")
      (node (ref "IC1") (pin "11") (pinfunction "PI9_11") (pintype "bidirectional"))
    )
    (net (code "134") (name "/uSD_CLK") (class "Default")
      (node (ref "IC1") (pin "141") (pinfunction "PC12_141") (pintype "bidirectional"))
    )
    (net (code "135") (name "/uSD_CMD") (class "Default")
      (node (ref "IC1") (pin "144") (pinfunction "PD2_144") (pintype "bidirectional"))
    )
    (net (code "136") (name "/uSD_D0") (class "Default")
      (node (ref "IC1") (pin "121") (pinfunction "PC8_121") (pintype "bidirectional"))
    )
    (net (code "137") (name "/uSD_D1") (class "Default")
      (node (ref "IC1") (pin "122") (pinfunction "PC9_122") (pintype "bidirectional"))
    )
    (net (code "138") (name "/uSD_D2") (class "Default")
      (node (ref "IC1") (pin "139") (pinfunction "PC10_139") (pintype "bidirectional"))
    )
    (net (code "139") (name "/uSD_D3") (class "Default")
      (node (ref "IC1") (pin "140") (pinfunction "PC11_140") (pintype "bidirectional"))
    )
    (net (code "141") (name "3V3") (class "Default")
      (node (ref "LS1") (pin "+") (pinfunction "+_+") (pintype "passive"))
      (node (ref "P2") (pin "1") (pinfunction "1_1") (pintype "passive"))
      (node (ref "R1") (pin "1") (pinfunction "1_1") (pintype "passive"))
      (node (ref "R5") (pin "1") (pinfunction "1_1") (pintype "passive"))
    )
    (net (code "142") (name "DSI_VDD12") (class "Default")
      (node (ref "C12") (pin "1") (pinfunction "1_1") (pintype "passive"))
      (node (ref "C13") (pin "1") (pinfunction "1_1") (pintype "passive"))
      (node (ref "C14") (pin "1") (pinfunction "1_1") (pintype "passive"))
      (node (ref "IC1") (pin "100") (pinfunction "VCAPDSI_100") (pintype "power_in"))
      (node (ref "IC1") (pin "106") (pinfunction "VDD12DSI_106") (pintype "power_in"))
    )
    (net (code "143") (name "GND") (class "Default")
      (node (ref "1") (pin "2") (pinfunction "2_2") (pintype "passive"))
      (node (ref "C1") (pin "2") (pinfunction "2_2") (pintype "passive"))
      (node (ref "C10") (pin "2") (pinfunction "2_2") (pintype "passive"))
      (node (ref "C11") (pin "2") (pinfunction "2_2") (pintype "passive"))
      (node (ref "C12") (pin "2") (pinfunction "2_2") (pintype "passive"))
      (node (ref "C13") (pin "2") (pinfunction "2_2") (pintype "passive"))
      (node (ref "C14") (pin "2") (pinfunction "2_2") (pintype "passive"))
      (node (ref "C15") (pin "2") (pinfunction "2_2") (pintype "passive"))
      (node (ref "C16") (pin "2") (pinfunction "2_2") (pintype "passive"))
      (node (ref "C17") (pin "2") (pinfunction "2_2") (pintype "passive"))
      (node (ref "C18") (pin "2") (pinfunction "2_2") (pintype "passive"))
      (node (ref "C19") (pin "1") (pinfunction "1_1") (pintype "passive"))
      (node (ref "C2") (pin "2") (pinfunction "2_2") (pintype "passive"))
      (node (ref "C20") (pin "1") (pinfunction "1_1") (pintype "passive"))
      (node (ref "C21") (pin "1") (pinfunction "1_1") (pintype "passive"))
      (node (ref "C22") (pin "2") (pinfunction "2_2") (pintype "passive"))
      (node (ref "C23") (pin "1") (pinfunction "1_1") (pintype "passive"))
      (node (ref "C24") (pin "2") (pinfunction "2_2") (pintype "passive"))
      (node (ref "C25") (pin "2") (pinfunction "2_2") (pintype "passive"))
      (node (ref "C26") (pin "2") (pinfunction "2_2") (pintype "passive"))
      (node (ref "C27") (pin "2") (pinfunction "2_2") (pintype "passive"))
      (node (ref "C28") (pin "2") (pinfunction "2_2") (pintype "passive"))
      (node (ref "C29") (pin "2") (pinfunction "2_2") (pintype "passive"))
      (node (ref "C3") (pin "2") (pinfunction "2_2") (pintype "passive"))
      (node (ref "C4") (pin "2") (pinfunction "2_2") (pintype "passive"))
      (node (ref "C5") (pin "2") (pinfunction "2_2") (pintype "passive"))
      (node (ref "C50") (pin "2") (pinfunction "2_2") (pintype "passive"))
      (node (ref "C6") (pin "2") (pinfunction "2_2") (pintype "passive"))
      (node (ref "C7") (pin "2") (pinfunction "2_2") (pintype "passive"))
      (node (ref "C8") (pin "2") (pinfunction "2_2") (pintype "passive"))
      (node (ref "C9") (pin "2") (pinfunction "2_2") (pintype "passive"))
      (node (ref "IC1") (pin "103") (pinfunction "VSSDSI_1_103") (pintype "power_in"))
      (node (ref "IC1") (pin "109") (pinfunction "VSSDSI_2_109") (pintype "power_in"))
      (node (ref "IC1") (pin "117") (pinfunction "VSS_6_117") (pintype "power_in"))
      (node (ref "IC1") (pin "130") (pinfunction "VSS_7_130") (pintype "power_in"))
      (node (ref "IC1") (pin "135") (pinfunction "VSS_8_135") (pintype "power_in"))
      (node (ref "IC1") (pin "14") (pinfunction "VSS_1_14") (pintype "power_in"))
      (node (ref "IC1") (pin "148") (pinfunction "VSS_9_148") (pintype "power_in"))
      (node (ref "IC1") (pin "158") (pinfunction "VSS_10_158") (pintype "power_in"))
      (node (ref "IC1") (pin "22") (pinfunction "VSS_2_22") (pintype "power_in"))
      (node (ref "IC1") (pin "37") (pinfunction "VSSA_37") (pintype "power_in"))
      (node (ref "IC1") (pin "61") (pinfunction "VSS_3_61") (pintype "power_in"))
      (node (ref "IC1") (pin "71") (pinfunction "VSS_4_71") (pintype "power_in"))
      (node (ref "IC1") (pin "95") (pinfunction "VSS_5_95") (pintype "power_in"))
      (node (ref "IC2") (pin "2") (pinfunction "2_2") (pintype "passive"))
      (node (ref "P2") (pin "3") (pinfunction "3_3") (pintype "passive"))
      (node (ref "Q1") (pin "2") (pinfunction "E_2") (pintype "passive"))
      (node (ref "R2") (pin "2") (pinfunction "2_2") (pintype "passive"))
    )
    (net (code "144") (name "Net-(C27-Pad1)") (class "Default")
      (node (ref "C27") (pin "1") (pinfunction "1_1") (pintype "passive"))
      (node (ref "R6") (pin "2") (pinfunction "2_2") (pintype "passive"))
      (node (ref "X1") (pin "1") (pinfunction "1_1") (pintype "passive"))
    )
    (net (code "145") (name "Net-(C28-Pad1)") (class "Default")
      (node (ref "C28") (pin "1") (pinfunction "1_1") (pintype "passive"))
      (node (ref "R7") (pin "2") (pinfunction "2_2") (pintype "passive"))
      (node (ref "X1") (pin "2") (pinfunction "2_2") (pintype "passive"))
    )
    (net (code "146") (name "Net-(C29-Pad1)") (class "Default")
      (node (ref "C29") (pin "1") (pinfunction "1_1") (pintype "passive"))
      (node (ref "R8") (pin "2") (pinfunction "2_2") (pintype "passive"))
      (node (ref "X2") (pin "1") (pinfunction "1_1") (pintype "passive"))
    )
    (net (code "147") (name "Net-(C50-Pad1)") (class "Default")
      (node (ref "C50") (pin "1") (pinfunction "1_1") (pintype "passive"))
      (node (ref "R9") (pin "2") (pinfunction "2_2") (pintype "passive"))
      (node (ref "X2") (pin "2") (pinfunction "2_2") (pintype "passive"))
    )
    (net (code "148") (name "Net-(IC1-BYPASS_REG)") (class "Default")
      (node (ref "1") (pin "1") (pinfunction "1_1") (pintype "passive"))
      (node (ref "IC1") (pin "48") (pinfunction "BYPASS_REG_48") (pintype "input"))
    )
    (net (code "149") (name "Net-(IC2-Pad1)") (class "Default")
      (node (ref "IC2") (pin "1") (pinfunction "1_1") (pintype "passive"))
      (node (ref "P1") (pin "3") (pinfunction "3_3") (pintype "passive"))
    )
    (net (code "150") (name "Net-(Q1-B)") (class "Default")
      (node (ref "Q1") (pin "1") (pinfunction "B_1") (pintype "passive"))
      (node (ref "R10") (pin "2") (pinfunction "2_2") (pintype "passive"))
    )
    (net (code "151") (name "Net-(Q1-C)") (class "Default")
      (node (ref "LS1") (pin "-") (pinfunction "-_-") (pintype "passive"))
      (node (ref "Q1") (pin "3") (pinfunction "C_3") (pintype "passive"))
    )
    (net (code "152") (name "VDD") (class "Default")
      (node (ref "C1") (pin "1") (pinfunction "1_1") (pintype "passive"))
      (node (ref "C10") (pin "1") (pinfunction "1_1") (pintype "passive"))
      (node (ref "C11") (pin "1") (pinfunction "1_1") (pintype "passive"))
      (node (ref "C15") (pin "1") (pinfunction "1_1") (pintype "passive"))
      (node (ref "C16") (pin "1") (pinfunction "1_1") (pintype "passive"))
      (node (ref "C17") (pin "1") (pinfunction "1_1") (pintype "passive"))
      (node (ref "C18") (pin "1") (pinfunction "1_1") (pintype "passive"))
      (node (ref "C19") (pin "2") (pinfunction "2_2") (pintype "passive"))
      (node (ref "C2") (pin "1") (pinfunction "1_1") (pintype "passive"))
      (node (ref "C20") (pin "2") (pinfunction "2_2") (pintype "passive"))
      (node (ref "C3") (pin "1") (pinfunction "1_1") (pintype "passive"))
      (node (ref "C4") (pin "1") (pinfunction "1_1") (pintype "passive"))
      (node (ref "C5") (pin "1") (pinfunction "1_1") (pintype "passive"))
      (node (ref "C6") (pin "1") (pinfunction "1_1") (pintype "passive"))
      (node (ref "C7") (pin "1") (pinfunction "1_1") (pintype "passive"))
      (node (ref "C8") (pin "1") (pinfunction "1_1") (pintype "passive"))
      (node (ref "C9") (pin "1") (pinfunction "1_1") (pintype "passive"))
      (node (ref "IC1") (pin "118") (pinfunction "VDDUSB_118") (pintype "power_in"))
      (node (ref "IC1") (pin "131") (pinfunction "VDD_9_131") (pintype "power_in"))
      (node (ref "IC1") (pin "136") (pinfunction "VDD_10_136") (pintype "power_in"))
      (node (ref "IC1") (pin "149") (pinfunction "VDDSDMMC_149") (pintype "power_in"))
      (node (ref "IC1") (pin "15") (pinfunction "VDD_1_15") (pintype "power_in"))
      (node (ref "IC1") (pin "159") (pinfunction "VDD_11_159") (pintype "power_in"))
      (node (ref "IC1") (pin "172") (pinfunction "VDD_12_172") (pintype "power_in"))
      (node (ref "IC1") (pin "23") (pinfunction "VDD_2_23") (pintype "power_in"))
      (node (ref "IC1") (pin "36") (pinfunction "VDD_3_36") (pintype "power_in"))
      (node (ref "IC1") (pin "49") (pinfunction "VDD_4_49") (pintype "power_in"))
      (node (ref "IC1") (pin "62") (pinfunction "VDD_5_62") (pintype "power_in"))
      (node (ref "IC1") (pin "72") (pinfunction "VDD_6_72") (pintype "power_in"))
      (node (ref "IC1") (pin "82") (pinfunction "VDD_7_82") (pintype "power_in"))
      (node (ref "IC1") (pin "96") (pinfunction "VDD_8_96") (pintype "power_in"))
      (node (ref "IC1") (pin "99") (pinfunction "VDDDSI_99") (pintype "power_in"))
      (node (ref "L1") (pin "2") (pinfunction "2_2") (pintype "passive"))
      (node (ref "P1") (pin "1") (pinfunction "1_1") (pintype "passive"))
    )
    (net (code "153") (name "VDDA") (class "Default")
      (node (ref "C21") (pin "2") (pinfunction "2_2") (pintype "passive"))
      (node (ref "C22") (pin "1") (pinfunction "1_1") (pintype "passive"))
      (node (ref "C23") (pin "2") (pinfunction "2_2") (pintype "passive"))
      (node (ref "C24") (pin "1") (pinfunction "1_1") (pintype "passive"))
      (node (ref "IC1") (pin "38") (pinfunction "VREF+_38") (pintype "power_in"))
      (node (ref "IC1") (pin "39") (pinfunction "VDDA_39") (pintype "power_in"))
      (node (ref "L1") (pin "1") (pinfunction "1_1") (pintype "passive"))
    )
    (net (code "154") (name "unconnected-(IC1-PB6-Pad164)") (class "Default")
      (node (ref "IC1") (pin "164") (pinfunction "PB6_164") (pintype "bidirectional+no_connect"))
    )
    (net (code "155") (name "unconnected-(IC1-PB7-Pad165)") (class "Default")
      (node (ref "IC1") (pin "165") (pinfunction "PB7_165") (pintype "bidirectional+no_connect"))
    )
    (net (code "156") (name "unconnected-(IC1-PD4-Pad146)") (class "Default")
      (node (ref "IC1") (pin "146") (pinfunction "PD4_146") (pintype "bidirectional+no_connect"))
    )
    (net (code "157") (name "unconnected-(IC1-PD5-Pad147)") (class "Default")
      (node (ref "IC1") (pin "147") (pinfunction "PD5_147") (pintype "bidirectional+no_connect"))
    )
    (net (code "158") (name "unconnected-(IC1-PD6-Pad150)") (class "Default")
      (node (ref "IC1") (pin "150") (pinfunction "PD6_150") (pintype "bidirectional+no_connect"))
    )
    (net (code "159") (name "unconnected-(IC1-PD7-Pad151)") (class "Default")
      (node (ref "IC1") (pin "151") (pinfunction "PD7_151") (pintype "bidirectional+no_connect"))
    )
    (net (code "160") (name "unconnected-(IC1-PF7-Pad25)") (class "Default")
      (node (ref "IC1") (pin "25") (pinfunction "PF7_25") (pintype "bidirectional+no_connect"))
    )
    (net (code "161") (name "unconnected-(IC1-PI3-Pad134)") (class "Default")
      (node (ref "IC1") (pin "134") (pinfunction "PI3_134") (pintype "bidirectional+no_connect"))
    )
    (net (code "162") (name "unconnected-(P2-Pad6)") (class "Default")
      (node (ref "P2") (pin "6") (pinfunction "6_6") (pintype "passive+no_connect"))
    )
  )
)
